# mcu_schematic.net
KiCad netlist of a schematic drawn in Altium Designer
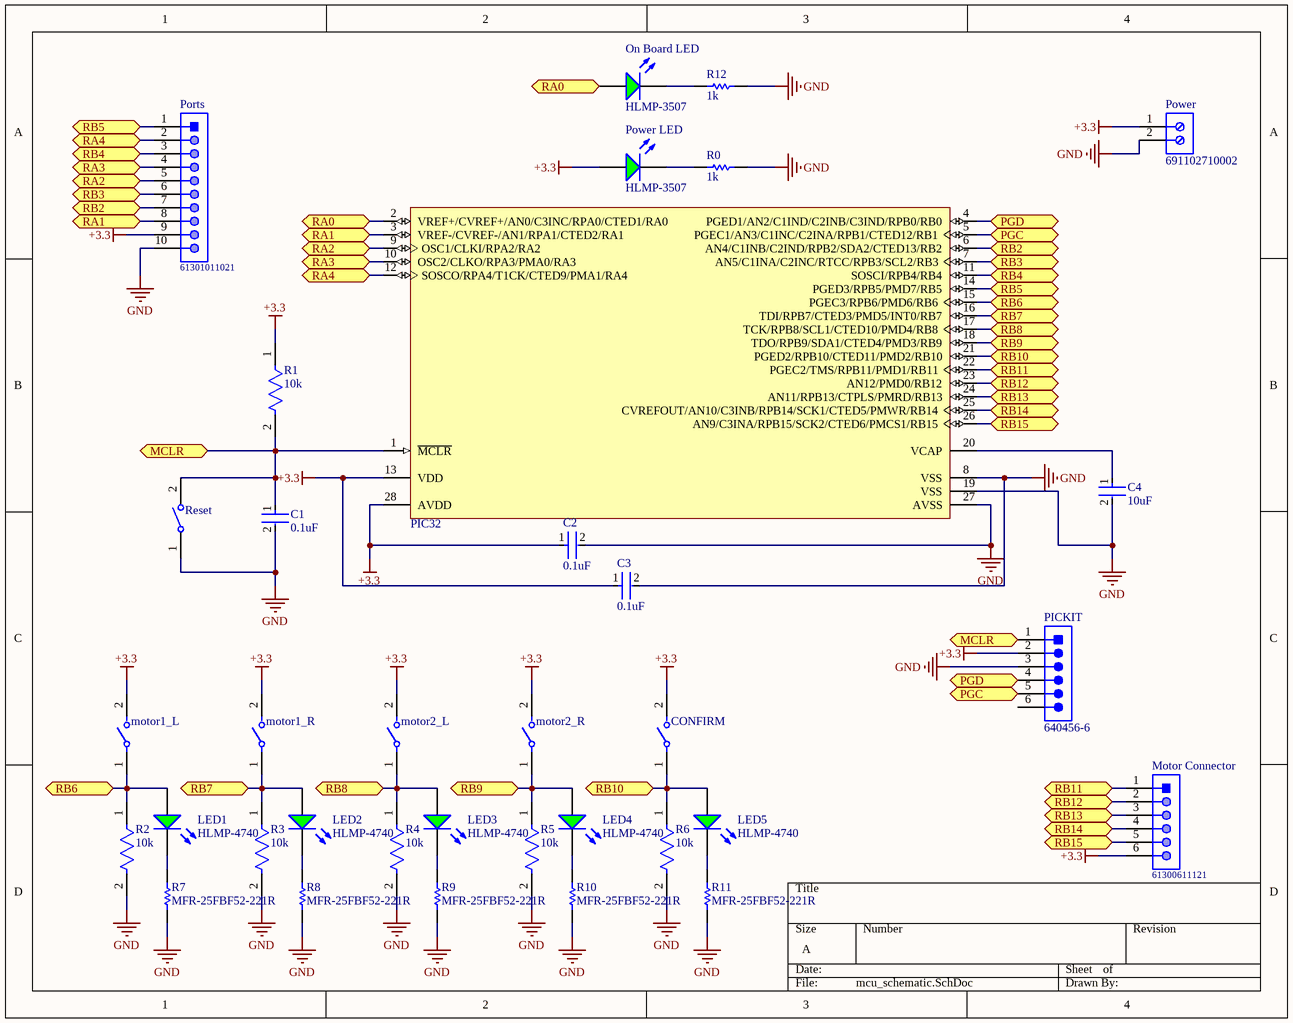
[diagram p0: mcu_schematic.SchDoc]

(export (version "E")
  (design (tool "Eeschema 10.0.6"))
  (components
    (comp (ref "C1")
      (value "0.1uF")
      (footprint "FP-C322C104K5R5TA-MFG")
      (description "CAP CER 0.1UF 50V X7R RADIAL\r\nC322C104K5R5TA")
      (fields (field (name "TOLERANCE") "10%") (field (name "VOLTAGE") "50V"))
      (libsource (lib "Altium Content Vault") (part "b4654b650e69147ec39a6b967a45e02"))
    )
    (comp (ref "C2")
      (value "0.1uF")
      (footprint "FP-C322C104K5R5TA-MFG")
      (description "CAP CER 0.1UF 50V X7R RADIAL\r\nC322C104K5R5TA")
      (fields (field (name "TOLERANCE") "10%") (field (name "VOLTAGE") "50V"))
      (libsource (lib "Altium Content Vault") (part "b4654b650e69147ec39a6b967a45e02"))
    )
    (comp (ref "C3")
      (value "0.1uF")
      (footprint "FP-C322C104K5R5TA-MFG")
      (description "CAP CER 0.1UF 50V X7R RADIAL\r\nC322C104K5R5TA")
      (fields (field (name "TOLERANCE") "10%") (field (name "VOLTAGE") "50V"))
      (libsource (lib "Altium Content Vault") (part "b4654b650e69147ec39a6b967a45e02"))
    )
    (comp (ref "C4")
      (value "10uF")
      (footprint "FP-C322C104K5R5TA-MFG")
      (description "CAP CER 0.1UF 50V X7R RADIAL\r\nC322C104K5R5TA")
      (fields (field (name "TOLERANCE") "10%") (field (name "VOLTAGE") "50V"))
      (libsource (lib "Altium Content Vault") (part "b4654b650e69147ec39a6b967a45e02"))
    )
    (comp (ref "CONFIRM")
      (value "FSM4JRT")
      (footprint "FP-FSM4JRT-MFG")
      (description "SWITCH TACTILE SPST-NO 0.05A 24V")
      (libsource (lib "Altium Content Vault") (part "bb27bde45df87f1f469753f287ef5ae"))
    )
    (comp (ref "LED1")
      (value "HLMP-4740")
      (footprint "AVAG-HLMP-4740")
      (description "T-1 3/4 (5 mm) Low Current LED Lamp, Green, 1.9 V, -20 to 100 degC, 2-Pin THD, RoHS, Bulk")
      (fields (field (name "MANUFACTURER") "AvagoTechnologies"))
      (libsource (lib "Altium Content Vault") (part "LED-GREEN-AK-2"))
    )
    (comp (ref "LED2")
      (value "HLMP-4740")
      (footprint "AVAG-HLMP-4740")
      (description "T-1 3/4 (5 mm) Low Current LED Lamp, Green, 1.9 V, -20 to 100 degC, 2-Pin THD, RoHS, Bulk")
      (fields (field (name "MANUFACTURER") "AvagoTechnologies"))
      (libsource (lib "Altium Content Vault") (part "LED-GREEN-AK-2"))
    )
    (comp (ref "LED3")
      (value "HLMP-4740")
      (footprint "AVAG-HLMP-4740")
      (description "T-1 3/4 (5 mm) Low Current LED Lamp, Green, 1.9 V, -20 to 100 degC, 2-Pin THD, RoHS, Bulk")
      (fields (field (name "MANUFACTURER") "AvagoTechnologies"))
      (libsource (lib "Altium Content Vault") (part "LED-GREEN-AK-2"))
    )
    (comp (ref "LED4")
      (value "HLMP-4740")
      (footprint "AVAG-HLMP-4740")
      (description "T-1 3/4 (5 mm) Low Current LED Lamp, Green, 1.9 V, -20 to 100 degC, 2-Pin THD, RoHS, Bulk")
      (fields (field (name "MANUFACTURER") "AvagoTechnologies"))
      (libsource (lib "Altium Content Vault") (part "LED-GREEN-AK-2"))
    )
    (comp (ref "LED5")
      (value "HLMP-4740")
      (footprint "AVAG-HLMP-4740")
      (description "T-1 3/4 (5 mm) Low Current LED Lamp, Green, 1.9 V, -20 to 100 degC, 2-Pin THD, RoHS, Bulk")
      (fields (field (name "MANUFACTURER") "AvagoTechnologies"))
      (libsource (lib "Altium Content Vault") (part "LED-GREEN-AK-2"))
    )
    (comp (ref "Motor Connector")
      (value "61300611121")
      (footprint "61300611121")
      (description "THT Vertical Pin Header WR-PHD, Pitch 2.54 mm, Single Row, 6 pins")
      (fields (field (name "MANUFACTURER") "Wurth Elektronik") (field (name "PUBLISHER") "WurthElektronik"))
      (libsource (lib "Altium Content Vault") (part "WE-CN-1P-M-R6"))
    )
    (comp (ref "motor1_L")
      (value "FSM4JRT")
      (footprint "FP-FSM4JRT-MFG")
      (description "SWITCH TACTILE SPST-NO 0.05A 24V")
      (libsource (lib "Altium Content Vault") (part "bb27bde45df87f1f469753f287ef5ae"))
    )
    (comp (ref "motor1_R")
      (value "FSM4JRT")
      (footprint "FP-FSM4JRT-MFG")
      (description "SWITCH TACTILE SPST-NO 0.05A 24V")
      (libsource (lib "Altium Content Vault") (part "bb27bde45df87f1f469753f287ef5ae"))
    )
    (comp (ref "motor2_L")
      (value "FSM4JRT")
      (footprint "FP-FSM4JRT-MFG")
      (description "SWITCH TACTILE SPST-NO 0.05A 24V")
      (libsource (lib "Altium Content Vault") (part "bb27bde45df87f1f469753f287ef5ae"))
    )
    (comp (ref "motor2_R")
      (value "FSM4JRT")
      (footprint "FP-FSM4JRT-MFG")
      (description "SWITCH TACTILE SPST-NO 0.05A 24V")
      (libsource (lib "Altium Content Vault") (part "bb27bde45df87f1f469753f287ef5ae"))
    )
    (comp (ref "On Board LED")
      (value "HLMP-3507")
      (footprint "AVAG-HLMP-3507")
      (description "T-1 3/4 (5 mm) Diffused LED Lamp, Green, 2.1 V, -20 to 100 degC, 2-Pin THD, RoHS, Bulk")
      (fields (field (name "MANUFACTURER") "Avago"))
      (libsource (lib "Altium Content Vault") (part "LED-GREEN-AK-2"))
    )
    (comp (ref "PIC32")
      (value "PIC32MX150F128B-I/SP")
      (footprint "MCHP-SPDIP-SP28")
      (fields (field (name "MANUFACTURER") "Microchip"))
      (libsource (lib "Altium Content Vault") (part "MCHP-PIC32MX1X0FXXXB-28"))
    )
    (comp (ref "PICKIT")
      (value "640456-6")
      (footprint "TECO-640456-6_V")
      (fields (field (name "MANUFACTURER") "TE Connectivity"))
      (libsource (lib "Altium Content Vault") (part "CN-1P-M-R6"))
    )
    (comp (ref "Ports")
      (value "61301011021")
      (footprint "61301011021")
      (description "THT Angled Pin Header WR-PHD, Pitch 2.54 mm, Single Row, 10 pins")
      (fields (field (name "MANUFACTURER") "Wurth Elektronik") (field (name "PUBLISHER") "WurthElektronik"))
      (libsource (lib "Altium Content Vault") (part "WE-CN-1P-M-R10"))
    )
    (comp (ref "Power")
      (value "691102710002")
      (footprint "691102710002")
      (description "Series 102 - 5.00 mm Horizontal Entry Modular with Pressure Clamp WR-TBL, 2 pin")
      (fields (field (name "MANUFACTURER") "Wurth Elektronik") (field (name "PUBLISHER") "WurthElektronik"))
      (libsource (lib "Altium Content Vault") (part "WE-CN-1P-F-TB2"))
    )
    (comp (ref "Power LED")
      (value "HLMP-3507")
      (footprint "AVAG-HLMP-3507")
      (description "T-1 3/4 (5 mm) Diffused LED Lamp, Green, 2.1 V, -20 to 100 degC, 2-Pin THD, RoHS, Bulk")
      (fields (field (name "MANUFACTURER") "Avago"))
      (libsource (lib "Altium Content Vault") (part "LED-GREEN-AK-2"))
    )
    (comp (ref "R0")
      (value "1k")
      (footprint "RESA60-630X240")
      (description "Axial Resistor, 1 KOhm, +/- 1%, 250 mW, -55 to 155 degC, 2-Pin THD, RoHS, Bulk\r\nMFR-25FBF52-1K")
      (fields (field (name "TOLERANCE") "1%"))
      (libsource (lib "Altium Content Vault") (part "RES-2"))
    )
    (comp (ref "R1")
      (value "10k")
      (footprint "FP-CF18-MFG")
      (description "RES 10K OHM 1/8W 5% CF AXIAL\r\nCF18JT10K0")
      (fields
        (field (name "MANUFACTURER PART NUMBER") "CF18JT10K0")
        (field (name "MANUFACTURER") "Stackpole Electronics")
      )
      (libsource (lib "Altium Content Vault") (part "1029c3af85768c4190bb7ad29bc67b5"))
    )
    (comp (ref "R2")
      (value "10k")
      (footprint "FP-CF18-MFG")
      (description "RES 10K OHM 1/8W 5% CF AXIAL\r\nCF18JT10K0")
      (fields
        (field (name "MANUFACTURER PART NUMBER") "CF18JT10K0")
        (field (name "MANUFACTURER") "Stackpole Electronics")
      )
      (libsource (lib "Altium Content Vault") (part "1029c3af85768c4190bb7ad29bc67b5"))
    )
    (comp (ref "R3")
      (value "10k")
      (footprint "FP-CF18-MFG")
      (description "RES 10K OHM 1/8W 5% CF AXIAL\r\nCF18JT10K0")
      (fields
        (field (name "MANUFACTURER PART NUMBER") "CF18JT10K0")
        (field (name "MANUFACTURER") "Stackpole Electronics")
      )
      (libsource (lib "Altium Content Vault") (part "1029c3af85768c4190bb7ad29bc67b5"))
    )
    (comp (ref "R4")
      (value "10k")
      (footprint "FP-CF18-MFG")
      (description "RES 10K OHM 1/8W 5% CF AXIAL\r\nCF18JT10K0")
      (fields
        (field (name "MANUFACTURER PART NUMBER") "CF18JT10K0")
        (field (name "MANUFACTURER") "Stackpole Electronics")
      )
      (libsource (lib "Altium Content Vault") (part "1029c3af85768c4190bb7ad29bc67b5"))
    )
    (comp (ref "R5")
      (value "10k")
      (footprint "FP-CF18-MFG")
      (description "RES 10K OHM 1/8W 5% CF AXIAL\r\nCF18JT10K0")
      (fields
        (field (name "MANUFACTURER PART NUMBER") "CF18JT10K0")
        (field (name "MANUFACTURER") "Stackpole Electronics")
      )
      (libsource (lib "Altium Content Vault") (part "1029c3af85768c4190bb7ad29bc67b5"))
    )
    (comp (ref "R6")
      (value "10k")
      (footprint "FP-CF18-MFG")
      (description "RES 10K OHM 1/8W 5% CF AXIAL\r\nCF18JT10K0")
      (fields
        (field (name "MANUFACTURER PART NUMBER") "CF18JT10K0")
        (field (name "MANUFACTURER") "Stackpole Electronics")
      )
      (libsource (lib "Altium Content Vault") (part "1029c3af85768c4190bb7ad29bc67b5"))
    )
    (comp (ref "R7")
      (value "MFR-25FBF52-221R")
      (footprint "RESA60-630X240")
      (description "Axial Resistor, 221 Ohm, +/- 1%, 250 mW, -55 to 155 degC, 2-Pin THD, RoHS, Bulk")
      (libsource (lib "Altium Content Vault") (part "RES-2"))
    )
    (comp (ref "R8")
      (value "MFR-25FBF52-221R")
      (footprint "RESA60-630X240")
      (description "Axial Resistor, 221 Ohm, +/- 1%, 250 mW, -55 to 155 degC, 2-Pin THD, RoHS, Bulk")
      (libsource (lib "Altium Content Vault") (part "RES-2"))
    )
    (comp (ref "R9")
      (value "MFR-25FBF52-221R")
      (footprint "RESA60-630X240")
      (description "Axial Resistor, 221 Ohm, +/- 1%, 250 mW, -55 to 155 degC, 2-Pin THD, RoHS, Bulk")
      (libsource (lib "Altium Content Vault") (part "RES-2"))
    )
    (comp (ref "R10")
      (value "MFR-25FBF52-221R")
      (footprint "RESA60-630X240")
      (description "Axial Resistor, 221 Ohm, +/- 1%, 250 mW, -55 to 155 degC, 2-Pin THD, RoHS, Bulk")
      (libsource (lib "Altium Content Vault") (part "RES-2"))
    )
    (comp (ref "R11")
      (value "MFR-25FBF52-221R")
      (footprint "RESA60-630X240")
      (description "Axial Resistor, 221 Ohm, +/- 1%, 250 mW, -55 to 155 degC, 2-Pin THD, RoHS, Bulk")
      (libsource (lib "Altium Content Vault") (part "RES-2"))
    )
    (comp (ref "R12")
      (value "1k")
      (footprint "RESA60-630X240")
      (description "Axial Resistor, 1 KOhm, +/- 1%, 250 mW, -55 to 155 degC, 2-Pin THD, RoHS, Bulk\r\nMFR-25FBF52-1K")
      (fields (field (name "TOLERANCE") "1%"))
      (libsource (lib "Altium Content Vault") (part "RES-2"))
    )
    (comp (ref "Reset")
      (value "~")
      (footprint "TECO-FSMSM-2_V")
      (description "FSMSM Push Button Switch, 50 mA, -35 to 85 degC, 2-Pin SMD, RoHS, Bulk\r\nFSMSM")
      (fields (field (name "MANUFACTURER") "TE Connectivity"))
      (libsource (lib "Altium Content Vault") (part "SW-SPST-2_C"))
    )
  )
  (nets
    (net (code "1") (name "+3.3") (class "Default")
      (node (ref "C2") (pin "1") (pinfunction "1_1") (pintype "passive"))
      (node (ref "C3") (pin "1") (pinfunction "1_1") (pintype "passive"))
      (node (ref "CONFIRM") (pin "2") (pinfunction "2_2") (pintype "passive"))
      (node (ref "Motor Connector") (pin "6") (pinfunction "6_6") (pintype "passive"))
      (node (ref "PIC32") (pin "13") (pinfunction "VDD_13") (pintype "power_in"))
      (node (ref "PIC32") (pin "28") (pinfunction "AVDD_28") (pintype "power_in"))
      (node (ref "PICKIT") (pin "2") (pinfunction "2_2") (pintype "passive"))
      (node (ref "Ports") (pin "9") (pinfunction "9_9") (pintype "passive"))
      (node (ref "Power") (pin "1") (pinfunction "1_1") (pintype "passive"))
      (node (ref "Power LED") (pin "1") (pinfunction "A_1") (pintype "passive"))
      (node (ref "R1") (pin "1") (pinfunction "1_1") (pintype "passive"))
      (node (ref "motor1_L") (pin "2") (pinfunction "2_2") (pintype "passive"))
      (node (ref "motor1_R") (pin "2") (pinfunction "2_2") (pintype "passive"))
      (node (ref "motor2_L") (pin "2") (pinfunction "2_2") (pintype "passive"))
      (node (ref "motor2_R") (pin "2") (pinfunction "2_2") (pintype "passive"))
    )
    (net (code "2") (name "/MCLR") (class "Default")
      (node (ref "C1") (pin "1") (pinfunction "1_1") (pintype "passive"))
      (node (ref "PIC32") (pin "1") (pinfunction "~{MCLR}_1") (pintype "input"))
      (node (ref "PICKIT") (pin "1") (pinfunction "1_1") (pintype "passive"))
      (node (ref "R1") (pin "2") (pinfunction "2_2") (pintype "passive"))
      (node (ref "Reset") (pin "2") (pinfunction "2_2") (pintype "passive"))
    )
    (net (code "3") (name "/PGC") (class "Default")
      (node (ref "PIC32") (pin "5") (pinfunction "PGEC1/AN3/C1INC/C2INA/RPB1/CTED12/RB1_5") (pintype "bidirectional"))
      (node (ref "PICKIT") (pin "5") (pinfunction "5_5") (pintype "passive"))
    )
    (net (code "4") (name "/PGD") (class "Default")
      (node (ref "PIC32") (pin "4") (pinfunction "PGED1/AN2/C1IND/C2INB/C3IND/RPB0/RB0_4") (pintype "bidirectional"))
      (node (ref "PICKIT") (pin "4") (pinfunction "4_4") (pintype "passive"))
    )
    (net (code "5") (name "/RA0") (class "Default")
      (node (ref "On Board LED") (pin "1") (pinfunction "A_1") (pintype "passive"))
      (node (ref "PIC32") (pin "2") (pinfunction "VREF+/CVREF+/AN0/C3INC/RPA0/CTED1/RA0_2") (pintype "bidirectional"))
    )
    (net (code "6") (name "/RA1") (class "Default")
      (node (ref "PIC32") (pin "3") (pinfunction "VREF-/CVREF-/AN1/RPA1/CTED2/RA1_3") (pintype "bidirectional"))
      (node (ref "Ports") (pin "8") (pinfunction "8_8") (pintype "passive"))
    )
    (net (code "7") (name "/RA2") (class "Default")
      (node (ref "PIC32") (pin "9") (pinfunction "OSC1/CLKI/RPA2/RA2_9") (pintype "bidirectional"))
      (node (ref "Ports") (pin "5") (pinfunction "5_5") (pintype "passive"))
    )
    (net (code "8") (name "/RA3") (class "Default")
      (node (ref "PIC32") (pin "10") (pinfunction "OSC2/CLKO/RPA3/PMA0/RA3_10") (pintype "bidirectional"))
      (node (ref "Ports") (pin "4") (pinfunction "4_4") (pintype "passive"))
    )
    (net (code "9") (name "/RA4") (class "Default")
      (node (ref "PIC32") (pin "12") (pinfunction "SOSCO/RPA4/T1CK/CTED9/PMA1/RA4_12") (pintype "bidirectional"))
      (node (ref "Ports") (pin "2") (pinfunction "2_2") (pintype "passive"))
    )
    (net (code "10") (name "/RB2") (class "Default")
      (node (ref "PIC32") (pin "6") (pinfunction "AN4/C1INB/C2IND/RPB2/SDA2/CTED13/RB2_6") (pintype "bidirectional"))
      (node (ref "Ports") (pin "7") (pinfunction "7_7") (pintype "passive"))
    )
    (net (code "11") (name "/RB3") (class "Default")
      (node (ref "PIC32") (pin "7") (pinfunction "AN5/C1INA/C2INC/RTCC/RPB3/SCL2/RB3_7") (pintype "bidirectional"))
      (node (ref "Ports") (pin "6") (pinfunction "6_6") (pintype "passive"))
    )
    (net (code "12") (name "/RB4") (class "Default")
      (node (ref "PIC32") (pin "11") (pinfunction "SOSCI/RPB4/RB4_11") (pintype "bidirectional"))
      (node (ref "Ports") (pin "3") (pinfunction "3_3") (pintype "passive"))
    )
    (net (code "13") (name "/RB5") (class "Default")
      (node (ref "PIC32") (pin "14") (pinfunction "PGED3/RPB5/PMD7/RB5_14") (pintype "bidirectional"))
      (node (ref "Ports") (pin "1") (pinfunction "1_1") (pintype "passive"))
    )
    (net (code "14") (name "/RB6") (class "Default")
      (node (ref "LED1") (pin "1") (pinfunction "A_1") (pintype "passive"))
      (node (ref "PIC32") (pin "15") (pinfunction "PGEC3/RPB6/PMD6/RB6_15") (pintype "bidirectional"))
      (node (ref "R2") (pin "1") (pinfunction "1_1") (pintype "passive"))
      (node (ref "motor1_L") (pin "1") (pinfunction "1_1") (pintype "passive"))
    )
    (net (code "15") (name "/RB7") (class "Default")
      (node (ref "LED2") (pin "1") (pinfunction "A_1") (pintype "passive"))
      (node (ref "PIC32") (pin "16") (pinfunction "TDI/RPB7/CTED3/PMD5/INT0/RB7_16") (pintype "bidirectional"))
      (node (ref "R3") (pin "1") (pinfunction "1_1") (pintype "passive"))
      (node (ref "motor1_R") (pin "1") (pinfunction "1_1") (pintype "passive"))
    )
    (net (code "16") (name "/RB8") (class "Default")
      (node (ref "LED3") (pin "1") (pinfunction "A_1") (pintype "passive"))
      (node (ref "PIC32") (pin "17") (pinfunction "TCK/RPB8/SCL1/CTED10/PMD4/RB8_17") (pintype "bidirectional"))
      (node (ref "R4") (pin "1") (pinfunction "1_1") (pintype "passive"))
      (node (ref "motor2_L") (pin "1") (pinfunction "1_1") (pintype "passive"))
    )
    (net (code "17") (name "/RB9") (class "Default")
      (node (ref "LED4") (pin "1") (pinfunction "A_1") (pintype "passive"))
      (node (ref "PIC32") (pin "18") (pinfunction "TDO/RPB9/SDA1/CTED4/PMD3/RB9_18") (pintype "bidirectional"))
      (node (ref "R5") (pin "1") (pinfunction "1_1") (pintype "passive"))
      (node (ref "motor2_R") (pin "1") (pinfunction "1_1") (pintype "passive"))
    )
    (net (code "18") (name "/RB10") (class "Default")
      (node (ref "CONFIRM") (pin "1") (pinfunction "1_1") (pintype "passive"))
      (node (ref "LED5") (pin "1") (pinfunction "A_1") (pintype "passive"))
      (node (ref "PIC32") (pin "21") (pinfunction "PGED2/RPB10/CTED11/PMD2/RB10_21") (pintype "bidirectional"))
      (node (ref "R6") (pin "1") (pinfunction "1_1") (pintype "passive"))
    )
    (net (code "19") (name "/RB11") (class "Default")
      (node (ref "Motor Connector") (pin "1") (pinfunction "1_1") (pintype "passive"))
      (node (ref "PIC32") (pin "22") (pinfunction "PGEC2/TMS/RPB11/PMD1/RB11_22") (pintype "bidirectional"))
    )
    (net (code "20") (name "/RB12") (class "Default")
      (node (ref "Motor Connector") (pin "2") (pinfunction "2_2") (pintype "passive"))
      (node (ref "PIC32") (pin "23") (pinfunction "AN12/PMD0/RB12_23") (pintype "bidirectional"))
    )
    (net (code "21") (name "/RB13") (class "Default")
      (node (ref "Motor Connector") (pin "3") (pinfunction "3_3") (pintype "passive"))
      (node (ref "PIC32") (pin "24") (pinfunction "AN11/RPB13/CTPLS/PMRD/RB13_24") (pintype "bidirectional"))
    )
    (net (code "22") (name "/RB14") (class "Default")
      (node (ref "Motor Connector") (pin "4") (pinfunction "4_4") (pintype "passive"))
      (node (ref "PIC32") (pin "25") (pinfunction "CVREFOUT/AN10/C3INB/RPB14/SCK1/CTED5/PMWR/RB14_25") (pintype "bidirectional"))
    )
    (net (code "23") (name "/RB15") (class "Default")
      (node (ref "Motor Connector") (pin "5") (pinfunction "5_5") (pintype "passive"))
      (node (ref "PIC32") (pin "26") (pinfunction "AN9/C3INA/RPB15/SCK2/CTED6/PMCS1/RB15_26") (pintype "bidirectional"))
    )
    (net (code "24") (name "GND") (class "Default")
      (node (ref "C1") (pin "2") (pinfunction "2_2") (pintype "passive"))
      (node (ref "C2") (pin "2") (pinfunction "2_2") (pintype "passive"))
      (node (ref "C3") (pin "2") (pinfunction "2_2") (pintype "passive"))
      (node (ref "C4") (pin "2") (pinfunction "2_2") (pintype "passive"))
      (node (ref "PIC32") (pin "19") (pinfunction "VSS_19") (pintype "power_in"))
      (node (ref "PIC32") (pin "27") (pinfunction "AVSS_27") (pintype "power_in"))
      (node (ref "PIC32") (pin "8") (pinfunction "VSS_8") (pintype "power_in"))
      (node (ref "PICKIT") (pin "3") (pinfunction "3_3") (pintype "passive"))
      (node (ref "Ports") (pin "10") (pinfunction "10_10") (pintype "passive"))
      (node (ref "Power") (pin "2") (pinfunction "2_2") (pintype "passive"))
      (node (ref "R0") (pin "2") (pinfunction "2_2") (pintype "passive"))
      (node (ref "R10") (pin "1") (pinfunction "1_1") (pintype "passive"))
      (node (ref "R11") (pin "1") (pinfunction "1_1") (pintype "passive"))
      (node (ref "R12") (pin "2") (pinfunction "2_2") (pintype "passive"))
      (node (ref "R2") (pin "2") (pinfunction "2_2") (pintype "passive"))
      (node (ref "R3") (pin "2") (pinfunction "2_2") (pintype "passive"))
      (node (ref "R4") (pin "2") (pinfunction "2_2") (pintype "passive"))
      (node (ref "R5") (pin "2") (pinfunction "2_2") (pintype "passive"))
      (node (ref "R6") (pin "2") (pinfunction "2_2") (pintype "passive"))
      (node (ref "R7") (pin "1") (pinfunction "1_1") (pintype "passive"))
      (node (ref "R8") (pin "1") (pinfunction "1_1") (pintype "passive"))
      (node (ref "R9") (pin "1") (pinfunction "1_1") (pintype "passive"))
      (node (ref "Reset") (pin "1") (pinfunction "1_1") (pintype "passive"))
    )
    (net (code "25") (name "Net-(LED1-K)") (class "Default")
      (node (ref "LED1") (pin "2") (pinfunction "K_2") (pintype "passive"))
      (node (ref "R7") (pin "2") (pinfunction "2_2") (pintype "passive"))
    )
    (net (code "26") (name "Net-(LED2-K)") (class "Default")
      (node (ref "LED2") (pin "2") (pinfunction "K_2") (pintype "passive"))
      (node (ref "R8") (pin "2") (pinfunction "2_2") (pintype "passive"))
    )
    (net (code "27") (name "Net-(LED3-K)") (class "Default")
      (node (ref "LED3") (pin "2") (pinfunction "K_2") (pintype "passive"))
      (node (ref "R9") (pin "2") (pinfunction "2_2") (pintype "passive"))
    )
    (net (code "28") (name "Net-(LED4-K)") (class "Default")
      (node (ref "LED4") (pin "2") (pinfunction "K_2") (pintype "passive"))
      (node (ref "R10") (pin "2") (pinfunction "2_2") (pintype "passive"))
    )
    (net (code "29") (name "Net-(LED5-K)") (class "Default")
      (node (ref "LED5") (pin "2") (pinfunction "K_2") (pintype "passive"))
      (node (ref "R11") (pin "2") (pinfunction "2_2") (pintype "passive"))
    )
    (net (code "30") (name "Net-(On Board LED-K)") (class "Default")
      (node (ref "On Board LED") (pin "2") (pinfunction "K_2") (pintype "passive"))
      (node (ref "R12") (pin "1") (pinfunction "1_1") (pintype "passive"))
    )
    (net (code "31") (name "Net-(PIC32-VCAP)") (class "Default")
      (node (ref "C4") (pin "1") (pinfunction "1_1") (pintype "passive"))
      (node (ref "PIC32") (pin "20") (pinfunction "VCAP_20") (pintype "passive"))
    )
    (net (code "32") (name "Net-(Power LED-K)") (class "Default")
      (node (ref "Power LED") (pin "2") (pinfunction "K_2") (pintype "passive"))
      (node (ref "R0") (pin "1") (pinfunction "1_1") (pintype "passive"))
    )
    (net (code "33") (name "unconnected-(PICKIT-Pad6)") (class "Default")
      (node (ref "PICKIT") (pin "6") (pinfunction "6_6") (pintype "passive"))
    )
  )
)
